# hm11bo.net
KiCad netlist of a schematic drawn in EAGLE
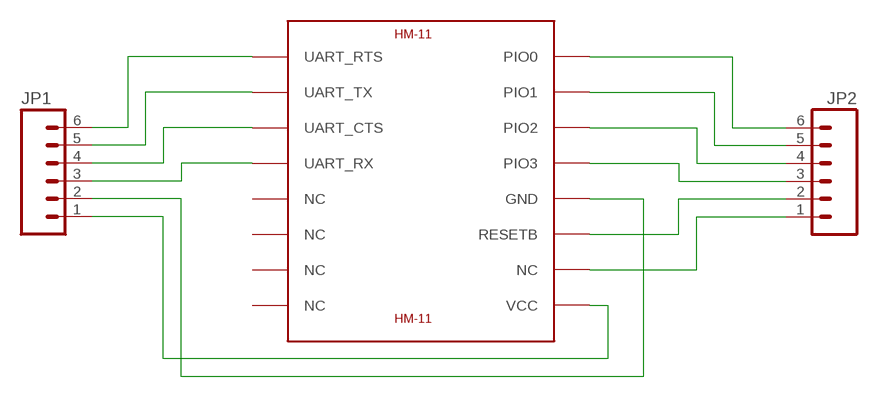
[diagram p0: schematic, sheet 1]

(export (version "E")
  (design (tool "Eeschema 10.0.6"))
  (components
    (comp (ref "JP1")
      (value "M06SIP")
      (footprint "eagle-import:1X06")
      (libsource (lib "eagle-import") (part "M06SIP"))
    )
    (comp (ref "JP2")
      (value "M06SIP")
      (footprint "eagle-import:1X06")
      (libsource (lib "eagle-import") (part "M06SIP"))
    )
    (comp (ref "U$1")
      (value "HM-11")
      (footprint "eagle-import:HM-11")
      (libsource (lib "eagle-import") (part "HM-11"))
    )
  )
  (nets
    (net (code "1") (name "Net-(JP1-Pad1)") (class "Default")
      (node (ref "JP1") (pin "1") (pinfunction "1_1") (pintype "passive"))
      (node (ref "U$1") (pin "VCC") (pinfunction "VCC_VCC") (pintype "bidirectional"))
    )
    (net (code "2") (name "Net-(JP1-Pad2)") (class "Default")
      (node (ref "JP1") (pin "2") (pinfunction "2_2") (pintype "passive"))
      (node (ref "U$1") (pin "GND") (pinfunction "GND_GND") (pintype "bidirectional"))
    )
    (net (code "3") (name "Net-(JP1-Pad3)") (class "Default")
      (node (ref "JP1") (pin "3") (pinfunction "3_3") (pintype "passive"))
      (node (ref "U$1") (pin "UART_RX") (pinfunction "UART_RX_UART_RX") (pintype "bidirectional"))
    )
    (net (code "4") (name "Net-(JP1-Pad4)") (class "Default")
      (node (ref "JP1") (pin "4") (pinfunction "4_4") (pintype "passive"))
      (node (ref "U$1") (pin "UART_CTS") (pinfunction "UART_CTS_UART_CTS") (pintype "bidirectional"))
    )
    (net (code "5") (name "Net-(JP1-Pad5)") (class "Default")
      (node (ref "JP1") (pin "5") (pinfunction "5_5") (pintype "passive"))
      (node (ref "U$1") (pin "UART_TX") (pinfunction "UART_TX_UART_TX") (pintype "bidirectional"))
    )
    (net (code "6") (name "Net-(JP1-Pad6)") (class "Default")
      (node (ref "JP1") (pin "6") (pinfunction "6_6") (pintype "passive"))
      (node (ref "U$1") (pin "UART_RTS") (pinfunction "UART_RTS_UART_RTS") (pintype "bidirectional"))
    )
    (net (code "7") (name "Net-(JP2-Pad1)") (class "Default")
      (node (ref "JP2") (pin "1") (pinfunction "1_1") (pintype "passive"))
      (node (ref "U$1") (pin "NC@10") (pinfunction "NC_NC@10") (pintype "bidirectional"))
    )
    (net (code "8") (name "Net-(JP2-Pad2)") (class "Default")
      (node (ref "JP2") (pin "2") (pinfunction "2_2") (pintype "passive"))
      (node (ref "U$1") (pin "RESETB") (pinfunction "RESETB_RESETB") (pintype "bidirectional"))
    )
    (net (code "9") (name "Net-(JP2-Pad3)") (class "Default")
      (node (ref "JP2") (pin "3") (pinfunction "3_3") (pintype "passive"))
      (node (ref "U$1") (pin "PIO3") (pinfunction "PIO3_PIO3") (pintype "bidirectional"))
    )
    (net (code "10") (name "Net-(JP2-Pad4)") (class "Default")
      (node (ref "JP2") (pin "4") (pinfunction "4_4") (pintype "passive"))
      (node (ref "U$1") (pin "PIO2") (pinfunction "PIO2_PIO2") (pintype "bidirectional"))
    )
    (net (code "11") (name "Net-(JP2-Pad5)") (class "Default")
      (node (ref "JP2") (pin "5") (pinfunction "5_5") (pintype "passive"))
      (node (ref "U$1") (pin "PIO1") (pinfunction "PIO1_PIO1") (pintype "bidirectional"))
    )
    (net (code "12") (name "Net-(JP2-Pad6)") (class "Default")
      (node (ref "JP2") (pin "6") (pinfunction "6_6") (pintype "passive"))
      (node (ref "U$1") (pin "PIO0") (pinfunction "PIO0_PIO0") (pintype "bidirectional"))
    )
    (net (code "13") (name "unconnected-(U$1-NC-PadNC@5)") (class "Default")
      (node (ref "U$1") (pin "NC@5") (pinfunction "NC_NC@5") (pintype "bidirectional"))
    )
    (net (code "14") (name "unconnected-(U$1-NC-PadNC@6)") (class "Default")
      (node (ref "U$1") (pin "NC@6") (pinfunction "NC_NC@6") (pintype "bidirectional"))
    )
    (net (code "15") (name "unconnected-(U$1-NC-PadNC@7)") (class "Default")
      (node (ref "U$1") (pin "NC@7") (pinfunction "NC_NC@7") (pintype "bidirectional"))
    )
    (net (code "16") (name "unconnected-(U$1-NC-PadNC@8)") (class "Default")
      (node (ref "U$1") (pin "NC@8") (pinfunction "NC_NC@8") (pintype "bidirectional"))
    )
  )
)
